# SinWaveAmplifier.net
KiCad netlist of a schematic drawn in Altium Designer
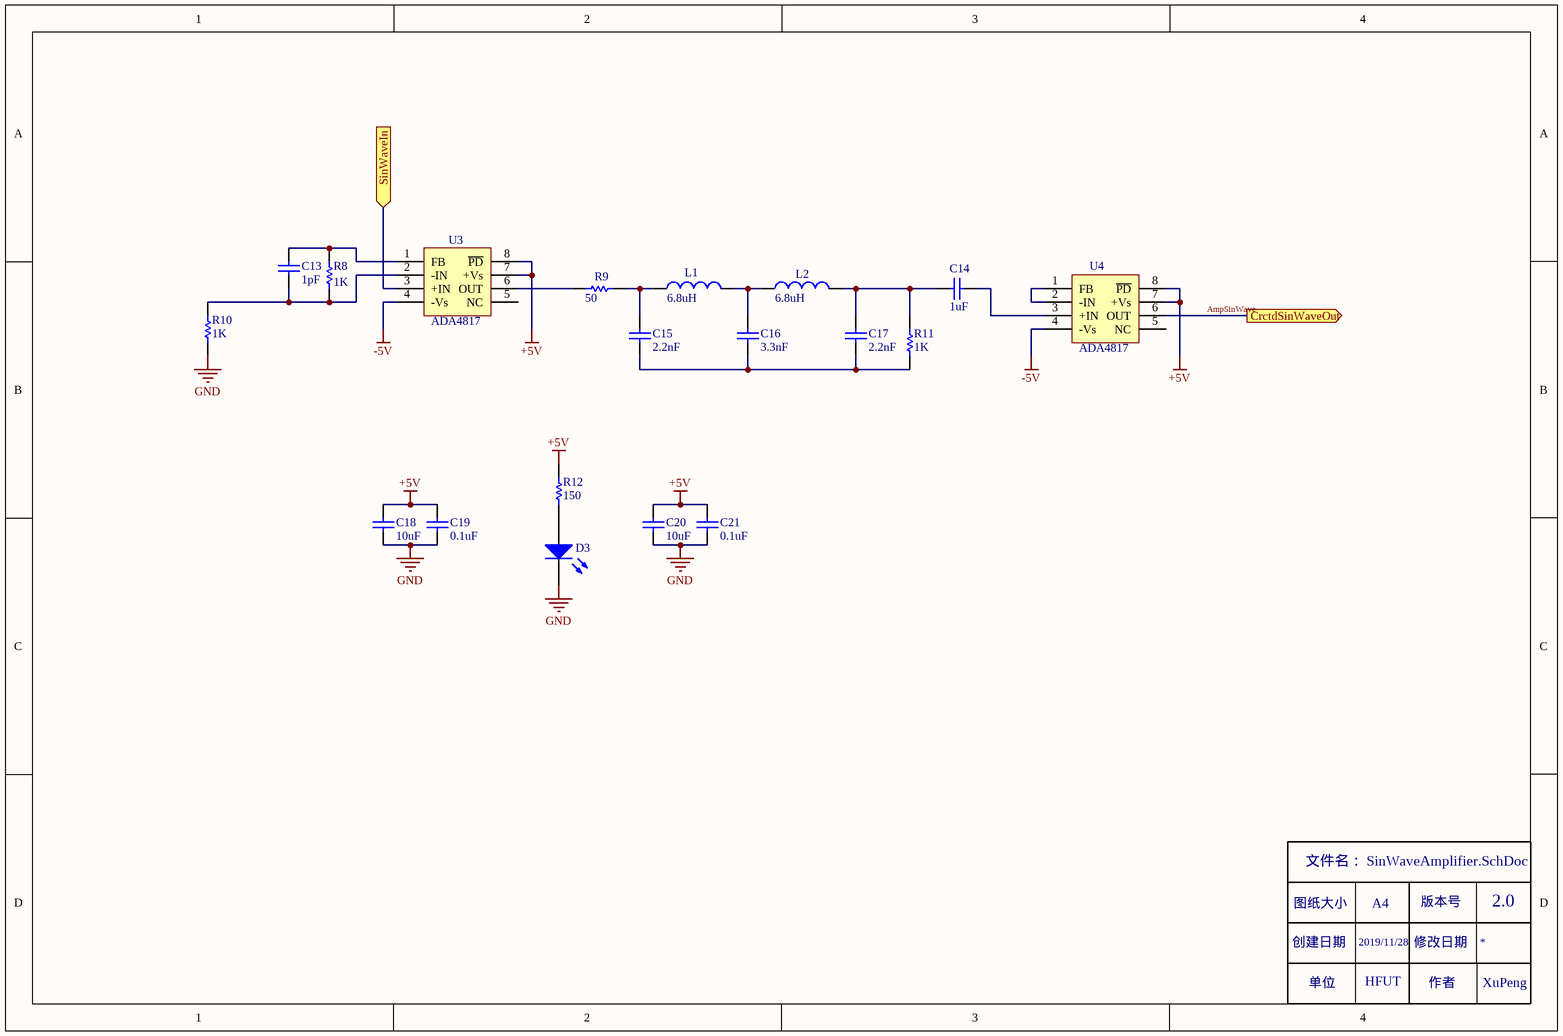
[diagram p0: SinWaveAmplifier.SchDoc]

(export (version "E")
  (design (tool "Eeschema 10.0.6"))
  (components
    (comp (ref "C13")
      (value "1pF")
      (footprint "C-RAD")
      (description "无极性电容")
      (fields (field (name "Comment") "Cap") (field (name "PUBLISHER") "Altium Limited"))
      (libsource (lib "Fszhang") (part "Cap"))
    )
    (comp (ref "C14")
      (value "1uF")
      (footprint "C-RAD")
      (description "无极性电容")
      (fields (field (name "Comment") "Cap") (field (name "PUBLISHER") "Altium Limited"))
      (libsource (lib "Fszhang") (part "Cap"))
    )
    (comp (ref "C15")
      (value "2.2nF")
      (footprint "C-RAD")
      (description "无极性电容")
      (fields (field (name "Comment") "Cap") (field (name "PUBLISHER") "Altium Limited"))
      (libsource (lib "Fszhang") (part "Cap"))
    )
    (comp (ref "C16")
      (value "3.3nF")
      (footprint "C-RAD")
      (description "无极性电容")
      (fields (field (name "Comment") "Cap") (field (name "PUBLISHER") "Altium Limited"))
      (libsource (lib "Fszhang") (part "Cap"))
    )
    (comp (ref "C17")
      (value "2.2nF")
      (footprint "C-RAD")
      (description "无极性电容")
      (fields (field (name "Comment") "Cap") (field (name "PUBLISHER") "Altium Limited"))
      (libsource (lib "Fszhang") (part "Cap"))
    )
    (comp (ref "C18")
      (value "10uF")
      (footprint "RB0.1/0.2")
      (description "无极性电容")
      (fields (field (name "Comment") "Cap") (field (name "PUBLISHER") "Altium Limited"))
      (libsource (lib "Fszhang") (part "Cap"))
    )
    (comp (ref "C19")
      (value "0.1uF")
      (footprint "C-RAD")
      (description "无极性电容")
      (fields (field (name "Comment") "Cap") (field (name "PUBLISHER") "Altium Limited"))
      (libsource (lib "Fszhang") (part "Cap"))
    )
    (comp (ref "C20")
      (value "10uF")
      (footprint "RB0.1/0.2")
      (description "无极性电容")
      (fields (field (name "Comment") "Cap") (field (name "PUBLISHER") "Altium Limited"))
      (libsource (lib "Fszhang") (part "Cap"))
    )
    (comp (ref "C21")
      (value "0.1uF")
      (footprint "C-RAD")
      (description "无极性电容")
      (fields (field (name "Comment") "Cap") (field (name "PUBLISHER") "Altium Limited"))
      (libsource (lib "Fszhang") (part "Cap"))
    )
    (comp (ref "D3")
      (value "LED0")
      (footprint "RB2.54/4")
      (description "Typical INFRARED GaAs LED")
      (fields (field (name "PUBLISHER") "Altium Limited"))
      (libsource (lib "Miscellaneous Devices") (part "LED0"))
    )
    (comp (ref "L1")
      (value "6.8uH")
      (footprint "PK0608-2.8/7")
      (description "Inductor")
      (fields (field (name "PUBLISHER") "Altium Limited"))
      (libsource (lib "Miscellaneous Devices") (part "Inductor"))
    )
    (comp (ref "L2")
      (value "6.8uH")
      (footprint "PK0608-2.8/7")
      (description "Inductor")
      (fields (field (name "PUBLISHER") "Altium Limited"))
      (libsource (lib "Miscellaneous Devices") (part "Inductor"))
    )
    (comp (ref "R8")
      (value "1K")
      (footprint "AXIAL-0.3")
      (description "Resistor")
      (fields (field (name "Comment") "Res1") (field (name "PUBLISHER") "Altium Limited"))
      (libsource (lib "Miscellaneous Devices") (part "Res1"))
    )
    (comp (ref "R9")
      (value "50")
      (footprint "AXIAL-0.3")
      (description "Resistor")
      (fields (field (name "Comment") "Res1") (field (name "PUBLISHER") "Altium Limited"))
      (libsource (lib "Miscellaneous Devices") (part "Res1"))
    )
    (comp (ref "R10")
      (value "1K")
      (footprint "AXIAL-0.3")
      (description "Resistor")
      (fields (field (name "Comment") "Res1") (field (name "PUBLISHER") "Altium Limited"))
      (libsource (lib "Miscellaneous Devices") (part "Res1"))
    )
    (comp (ref "R11")
      (value "1K")
      (footprint "AXIAL-0.3")
      (description "Resistor")
      (fields (field (name "Comment") "Res1") (field (name "PUBLISHER") "Altium Limited"))
      (libsource (lib "Miscellaneous Devices") (part "Res1"))
    )
    (comp (ref "R12")
      (value "150")
      (footprint "AXIAL-0.3")
      (description "Resistor")
      (fields (field (name "Comment") "Res1") (field (name "PUBLISHER") "Altium Limited"))
      (libsource (lib "Miscellaneous Devices") (part "Res1"))
    )
    (comp (ref "U3")
      (value "ADA4817")
      (footprint "SOP8")
      (libsource (lib "ElectricalConductivityMeterIntLib") (part "ADA4817"))
    )
    (comp (ref "U4")
      (value "ADA4817")
      (footprint "SOP8")
      (libsource (lib "ElectricalConductivityMeterIntLib") (part "ADA4817"))
    )
  )
  (nets
    (net (code "1") (name "+5V") (class "Default")
      (node (ref "C18") (pin "2") (pinfunction "2_2") (pintype "passive"))
      (node (ref "C19") (pin "2") (pinfunction "2_2") (pintype "passive"))
      (node (ref "C20") (pin "2") (pinfunction "2_2") (pintype "passive"))
      (node (ref "C21") (pin "2") (pinfunction "2_2") (pintype "passive"))
      (node (ref "R12") (pin "2") (pinfunction "2_2") (pintype "passive"))
      (node (ref "U3") (pin "7") (pinfunction "+Vs_7") (pintype "passive"))
      (node (ref "U3") (pin "8") (pinfunction "~{PD}_8") (pintype "passive"))
      (node (ref "U4") (pin "7") (pinfunction "+Vs_7") (pintype "passive"))
      (node (ref "U4") (pin "8") (pinfunction "~{PD}_8") (pintype "passive"))
    )
    (net (code "2") (name "-5V") (class "Default")
      (node (ref "U3") (pin "4") (pinfunction "-Vs_4") (pintype "passive"))
      (node (ref "U4") (pin "4") (pinfunction "-Vs_4") (pintype "passive"))
    )
    (net (code "3") (name "/AmpSinWave") (class "Default")
      (node (ref "U4") (pin "6") (pinfunction "OUT_6") (pintype "passive"))
    )
    (net (code "4") (name "/SinWaveIn") (class "Default")
      (node (ref "U3") (pin "3") (pinfunction "+IN_3") (pintype "passive"))
    )
    (net (code "5") (name "GND") (class "Default")
      (node (ref "C18") (pin "1") (pinfunction "1_1") (pintype "passive"))
      (node (ref "C19") (pin "1") (pinfunction "1_1") (pintype "passive"))
      (node (ref "C20") (pin "1") (pinfunction "1_1") (pintype "passive"))
      (node (ref "C21") (pin "1") (pinfunction "1_1") (pintype "passive"))
      (node (ref "D3") (pin "2") (pinfunction "K_2") (pintype "passive"))
      (node (ref "R10") (pin "1") (pinfunction "1_1") (pintype "passive"))
    )
    (net (code "6") (name "Net-(C14-Pad1)") (class "Default")
      (node (ref "C14") (pin "1") (pinfunction "1_1") (pintype "passive"))
      (node (ref "C17") (pin "2") (pinfunction "2_2") (pintype "passive"))
      (node (ref "L2") (pin "2") (pinfunction "2_2") (pintype "passive"))
      (node (ref "R11") (pin "2") (pinfunction "2_2") (pintype "passive"))
    )
    (net (code "7") (name "Net-(C15-Pad1)") (class "Default")
      (node (ref "C15") (pin "1") (pinfunction "1_1") (pintype "passive"))
      (node (ref "C16") (pin "1") (pinfunction "1_1") (pintype "passive"))
      (node (ref "C17") (pin "1") (pinfunction "1_1") (pintype "passive"))
      (node (ref "R11") (pin "1") (pinfunction "1_1") (pintype "passive"))
    )
    (net (code "8") (name "Net-(C15-Pad2)") (class "Default")
      (node (ref "C15") (pin "2") (pinfunction "2_2") (pintype "passive"))
      (node (ref "L1") (pin "1") (pinfunction "1_1") (pintype "passive"))
      (node (ref "R9") (pin "2") (pinfunction "2_2") (pintype "passive"))
    )
    (net (code "9") (name "Net-(C16-Pad2)") (class "Default")
      (node (ref "C16") (pin "2") (pinfunction "2_2") (pintype "passive"))
      (node (ref "L1") (pin "2") (pinfunction "2_2") (pintype "passive"))
      (node (ref "L2") (pin "1") (pinfunction "1_1") (pintype "passive"))
    )
    (net (code "10") (name "Net-(D3-A)") (class "Default")
      (node (ref "D3") (pin "1") (pinfunction "A_1") (pintype "passive"))
      (node (ref "R12") (pin "1") (pinfunction "1_1") (pintype "passive"))
    )
    (net (code "11") (name "Net-(U3--IN)") (class "Default")
      (node (ref "C13") (pin "1") (pinfunction "1_1") (pintype "passive"))
      (node (ref "R10") (pin "2") (pinfunction "2_2") (pintype "passive"))
      (node (ref "R8") (pin "1") (pinfunction "1_1") (pintype "passive"))
      (node (ref "U3") (pin "2") (pinfunction "-IN_2") (pintype "passive"))
    )
    (net (code "12") (name "Net-(U3-FB)") (class "Default")
      (node (ref "C13") (pin "2") (pinfunction "2_2") (pintype "passive"))
      (node (ref "R8") (pin "2") (pinfunction "2_2") (pintype "passive"))
      (node (ref "U3") (pin "1") (pinfunction "FB_1") (pintype "passive"))
    )
    (net (code "13") (name "Net-(U3-OUT)") (class "Default")
      (node (ref "R9") (pin "1") (pinfunction "1_1") (pintype "passive"))
      (node (ref "U3") (pin "6") (pinfunction "OUT_6") (pintype "passive"))
    )
    (net (code "14") (name "Net-(U4-+IN)") (class "Default")
      (node (ref "C14") (pin "2") (pinfunction "2_2") (pintype "passive"))
      (node (ref "U4") (pin "3") (pinfunction "+IN_3") (pintype "passive"))
    )
    (net (code "15") (name "Net-(U4--IN)") (class "Default")
      (node (ref "U4") (pin "1") (pinfunction "FB_1") (pintype "passive"))
      (node (ref "U4") (pin "2") (pinfunction "-IN_2") (pintype "passive"))
    )
    (net (code "16") (name "unconnected-(U3-NC-Pad5)") (class "Default")
      (node (ref "U3") (pin "5") (pinfunction "NC_5") (pintype "passive"))
    )
    (net (code "17") (name "unconnected-(U4-NC-Pad5)") (class "Default")
      (node (ref "U4") (pin "5") (pinfunction "NC_5") (pintype "passive"))
    )
  )
)
